# M_UmarKhtam_sensor.net
KiCad netlist of a schematic drawn in EAGLE
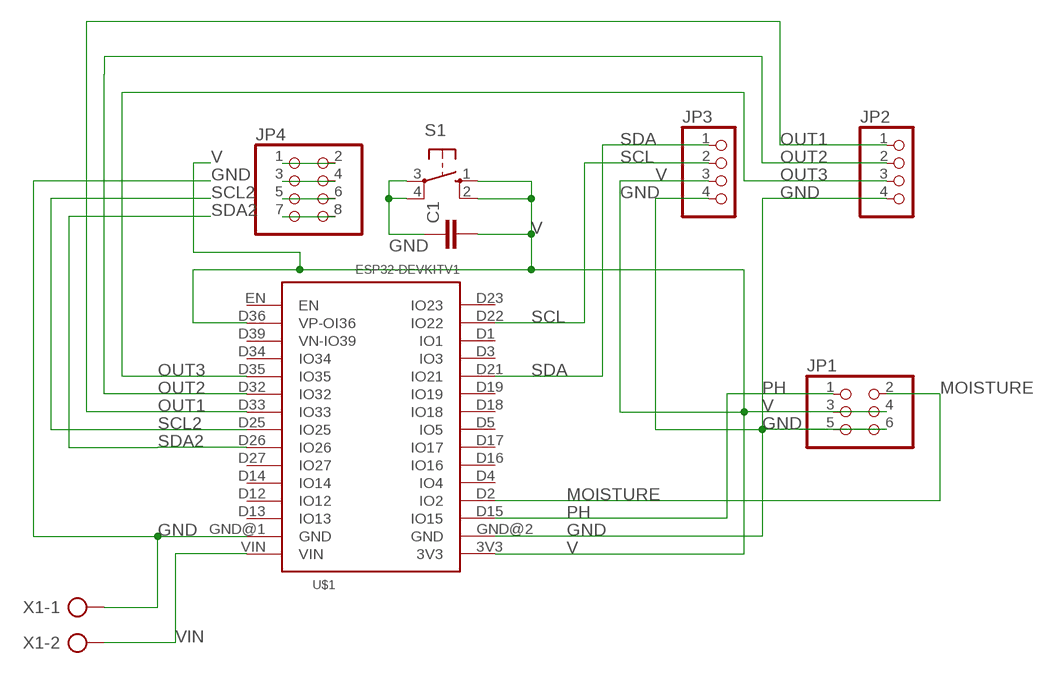
[diagram p0: schematic, sheet 1]

(export (version "E")
  (design (tool "Eeschema 10.0.6"))
  (components
    (comp (ref "C1")
      (value "C-EU050-030X075")
      (footprint "eagle-import:C050-030X075")
      (libsource (lib "eagle-import") (part "C-EU050-030X075"))
    )
    (comp (ref "JP1")
      (value "PINHD-2X3")
      (footprint "eagle-import:2X03")
      (libsource (lib "eagle-import") (part "PINHD-2X3"))
    )
    (comp (ref "JP2")
      (value "PINHD-1X4")
      (footprint "eagle-import:1X04")
      (libsource (lib "eagle-import") (part "PINHD-1X4"))
    )
    (comp (ref "JP3")
      (value "PINHD-1X4")
      (footprint "eagle-import:1X04")
      (libsource (lib "eagle-import") (part "PINHD-1X4"))
    )
    (comp (ref "JP4")
      (value "PINHD-2X4")
      (footprint "eagle-import:2X04")
      (libsource (lib "eagle-import") (part "PINHD-2X4"))
    )
    (comp (ref "S1")
      (value "10-XX")
      (footprint "eagle-import:B3F-10XX")
      (fields (field (name "MPN") "B3F-1000"))
      (libsource (lib "eagle-import") (part "10-XX"))
    )
    (comp (ref "U$1")
      (value "ESP32DEVKITV1")
      (footprint "eagle-import:ESP32-DEVKITV1")
      (libsource (lib "eagle-import") (part "ESP32DEVKITV1"))
    )
    (comp (ref "X1")
      (value "AK300/2")
      (footprint "eagle-import:AK300_2")
      (libsource (lib "eagle-import") (part "AK300/2"))
    )
  )
  (nets
    (net (code "1") (name "/GND") (class "Default")
      (node (ref "C1") (pin "1") (pinfunction "1_1") (pintype "passive"))
      (node (ref "JP1") (pin "5") (pinfunction "5_5") (pintype "passive"))
      (node (ref "JP1") (pin "6") (pinfunction "6_6") (pintype "passive"))
      (node (ref "JP2") (pin "4") (pinfunction "4_4") (pintype "passive"))
      (node (ref "JP3") (pin "4") (pinfunction "4_4") (pintype "passive"))
      (node (ref "JP4") (pin "3") (pinfunction "3_3") (pintype "passive"))
      (node (ref "JP4") (pin "4") (pinfunction "4_4") (pintype "passive"))
      (node (ref "S1") (pin "3") (pinfunction "P_3") (pintype "passive"))
      (node (ref "S1") (pin "4") (pinfunction "P1_4") (pintype "passive"))
      (node (ref "U$1") (pin "GND@1") (pinfunction "GND_GND@1") (pintype "bidirectional"))
      (node (ref "U$1") (pin "GND@2") (pinfunction "GND_GND@2") (pintype "bidirectional"))
      (node (ref "X1") (pin "1") (pinfunction "KL_1") (pintype "passive"))
    )
    (net (code "2") (name "/MOISTURE") (class "Default")
      (node (ref "JP1") (pin "2") (pinfunction "2_2") (pintype "passive"))
      (node (ref "U$1") (pin "D2") (pinfunction "IO2_D2") (pintype "bidirectional"))
    )
    (net (code "3") (name "/OUT1") (class "Default")
      (node (ref "JP2") (pin "1") (pinfunction "1_1") (pintype "passive"))
      (node (ref "U$1") (pin "D33") (pinfunction "IO33_D33") (pintype "bidirectional"))
    )
    (net (code "4") (name "/OUT2") (class "Default")
      (node (ref "JP2") (pin "2") (pinfunction "2_2") (pintype "passive"))
      (node (ref "U$1") (pin "D32") (pinfunction "IO32_D32") (pintype "bidirectional"))
    )
    (net (code "5") (name "/OUT3") (class "Default")
      (node (ref "JP2") (pin "3") (pinfunction "3_3") (pintype "passive"))
      (node (ref "U$1") (pin "D35") (pinfunction "IO35_D35") (pintype "bidirectional"))
    )
    (net (code "6") (name "/PH") (class "Default")
      (node (ref "JP1") (pin "1") (pinfunction "1_1") (pintype "passive"))
      (node (ref "U$1") (pin "D15") (pinfunction "IO15_D15") (pintype "bidirectional"))
    )
    (net (code "7") (name "/SCL") (class "Default")
      (node (ref "JP3") (pin "2") (pinfunction "2_2") (pintype "passive"))
      (node (ref "U$1") (pin "D22") (pinfunction "IO22_D22") (pintype "bidirectional"))
    )
    (net (code "8") (name "/SCL2") (class "Default")
      (node (ref "JP4") (pin "5") (pinfunction "5_5") (pintype "passive"))
      (node (ref "JP4") (pin "6") (pinfunction "6_6") (pintype "passive"))
      (node (ref "U$1") (pin "D25") (pinfunction "IO25_D25") (pintype "bidirectional"))
    )
    (net (code "9") (name "/SDA") (class "Default")
      (node (ref "JP3") (pin "1") (pinfunction "1_1") (pintype "passive"))
      (node (ref "U$1") (pin "D21") (pinfunction "IO21_D21") (pintype "bidirectional"))
    )
    (net (code "10") (name "/SDA2") (class "Default")
      (node (ref "JP4") (pin "7") (pinfunction "7_7") (pintype "passive"))
      (node (ref "JP4") (pin "8") (pinfunction "8_8") (pintype "passive"))
      (node (ref "U$1") (pin "D26") (pinfunction "IO26_D26") (pintype "bidirectional"))
    )
    (net (code "11") (name "/V") (class "Default")
      (node (ref "C1") (pin "2") (pinfunction "2_2") (pintype "passive"))
      (node (ref "JP1") (pin "3") (pinfunction "3_3") (pintype "passive"))
      (node (ref "JP1") (pin "4") (pinfunction "4_4") (pintype "passive"))
      (node (ref "JP3") (pin "3") (pinfunction "3_3") (pintype "passive"))
      (node (ref "JP4") (pin "1") (pinfunction "1_1") (pintype "passive"))
      (node (ref "JP4") (pin "2") (pinfunction "2_2") (pintype "passive"))
      (node (ref "S1") (pin "1") (pinfunction "S_1") (pintype "passive"))
      (node (ref "S1") (pin "2") (pinfunction "S1_2") (pintype "passive"))
      (node (ref "U$1") (pin "3V3") (pinfunction "3V3_3V3") (pintype "bidirectional"))
      (node (ref "U$1") (pin "D36") (pinfunction "VP-OI36_D36") (pintype "bidirectional"))
    )
    (net (code "12") (name "/VIN") (class "Default")
      (node (ref "U$1") (pin "VIN") (pinfunction "VIN_VIN") (pintype "bidirectional"))
      (node (ref "X1") (pin "2") (pinfunction "KL_2") (pintype "passive"))
    )
    (net (code "13") (name "unconnected-(U$1-IO1-PadD1)") (class "Default")
      (node (ref "U$1") (pin "D1") (pinfunction "IO1_D1") (pintype "bidirectional"))
    )
    (net (code "14") (name "unconnected-(U$1-IO3-PadD3)") (class "Default")
      (node (ref "U$1") (pin "D3") (pinfunction "IO3_D3") (pintype "bidirectional"))
    )
    (net (code "15") (name "unconnected-(U$1-IO4-PadD4)") (class "Default")
      (node (ref "U$1") (pin "D4") (pinfunction "IO4_D4") (pintype "bidirectional"))
    )
    (net (code "16") (name "unconnected-(U$1-IO5-PadD5)") (class "Default")
      (node (ref "U$1") (pin "D5") (pinfunction "IO5_D5") (pintype "bidirectional"))
    )
    (net (code "17") (name "unconnected-(U$1-IO12-PadD12)") (class "Default")
      (node (ref "U$1") (pin "D12") (pinfunction "IO12_D12") (pintype "bidirectional"))
    )
    (net (code "18") (name "unconnected-(U$1-IO13-PadD13)") (class "Default")
      (node (ref "U$1") (pin "D13") (pinfunction "IO13_D13") (pintype "bidirectional"))
    )
    (net (code "19") (name "unconnected-(U$1-IO14-PadD14)") (class "Default")
      (node (ref "U$1") (pin "D14") (pinfunction "IO14_D14") (pintype "bidirectional"))
    )
    (net (code "20") (name "unconnected-(U$1-IO16-PadD16)") (class "Default")
      (node (ref "U$1") (pin "D16") (pinfunction "IO16_D16") (pintype "bidirectional"))
    )
    (net (code "21") (name "unconnected-(U$1-IO17-PadD17)") (class "Default")
      (node (ref "U$1") (pin "D17") (pinfunction "IO17_D17") (pintype "bidirectional"))
    )
    (net (code "22") (name "unconnected-(U$1-IO18-PadD18)") (class "Default")
      (node (ref "U$1") (pin "D18") (pinfunction "IO18_D18") (pintype "bidirectional"))
    )
    (net (code "23") (name "unconnected-(U$1-IO19-PadD19)") (class "Default")
      (node (ref "U$1") (pin "D19") (pinfunction "IO19_D19") (pintype "bidirectional"))
    )
    (net (code "24") (name "unconnected-(U$1-IO23-PadD23)") (class "Default")
      (node (ref "U$1") (pin "D23") (pinfunction "IO23_D23") (pintype "bidirectional"))
    )
    (net (code "25") (name "unconnected-(U$1-IO27-PadD27)") (class "Default")
      (node (ref "U$1") (pin "D27") (pinfunction "IO27_D27") (pintype "bidirectional"))
    )
    (net (code "26") (name "unconnected-(U$1-IO34-PadD34)") (class "Default")
      (node (ref "U$1") (pin "D34") (pinfunction "IO34_D34") (pintype "bidirectional"))
    )
    (net (code "27") (name "unconnected-(U$1-PadEN)") (class "Default")
      (node (ref "U$1") (pin "EN") (pinfunction "EN_EN") (pintype "bidirectional"))
    )
    (net (code "28") (name "unconnected-(U$1-VN-IO39-PadD39)") (class "Default")
      (node (ref "U$1") (pin "D39") (pinfunction "VN-IO39_D39") (pintype "bidirectional"))
    )
  )
)
